# Dual_H_Bridge_and_Accessories.net
KiCad netlist of a schematic drawn in EAGLE
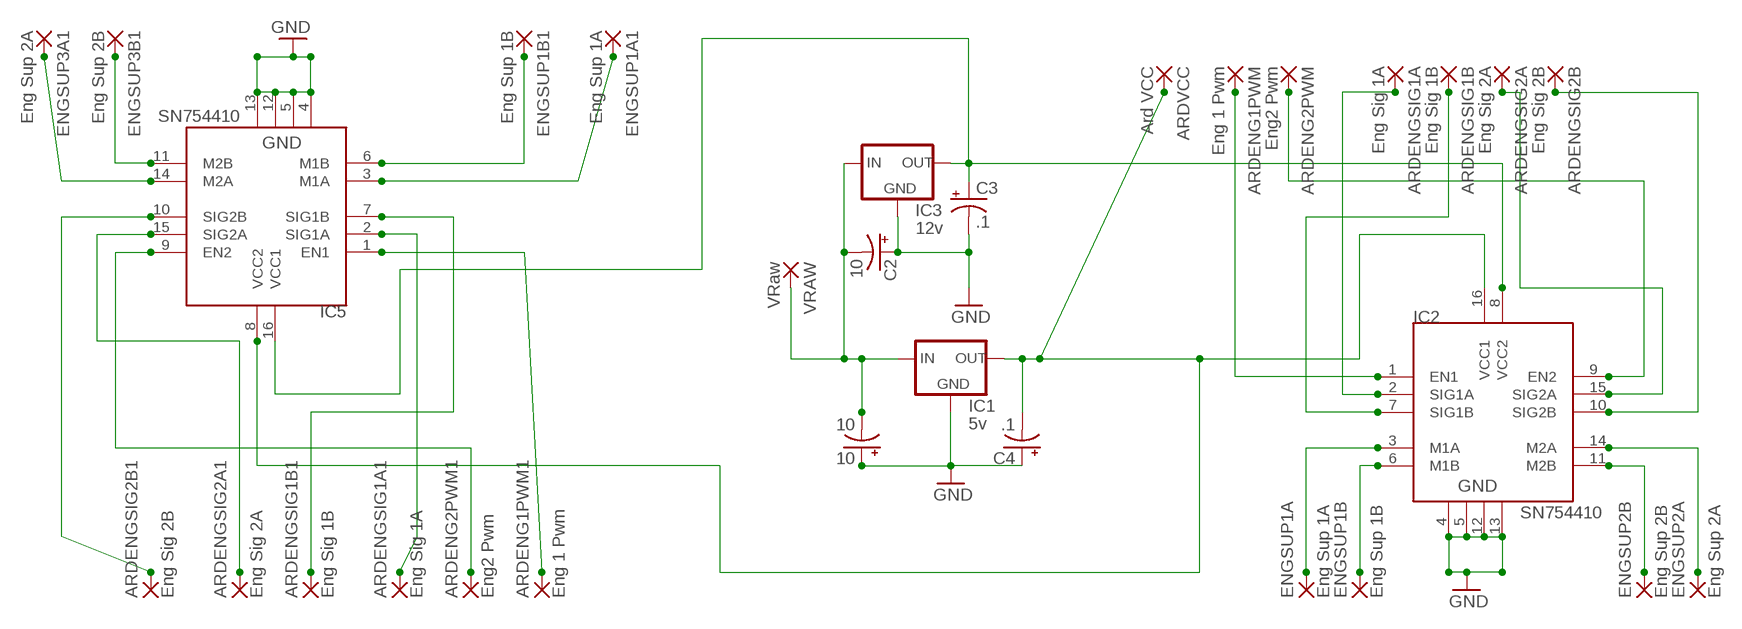
[diagram p0: schematic, sheet 1]

(export (version "E")
  (design (tool "Eeschema 10.0.6"))
  (components
    (comp (ref "10")
      (value "10")
      (footprint "eagle-import:CPOL-RADIAL-10UF-25V")
      (libsource (lib "eagle-import") (part "CAP_POLPTH2"))
    )
    (comp (ref "ARDENG1PWM")
      (value "Eng 1 Pwm")
      (footprint "eagle-import:3,17_1,3")
      (libsource (lib "eagle-import") (part "3,17/1,3"))
    )
    (comp (ref "ARDENG1PWM1")
      (value "Eng 1 Pwm")
      (footprint "eagle-import:3,17_1,3")
      (libsource (lib "eagle-import") (part "3,17/1,3"))
    )
    (comp (ref "ARDENG2PWM")
      (value "Eng2 Pwm")
      (footprint "eagle-import:3,17_1,3")
      (libsource (lib "eagle-import") (part "3,17/1,3"))
    )
    (comp (ref "ARDENG2PWM1")
      (value "Eng2 Pwm")
      (footprint "eagle-import:3,17_1,3")
      (libsource (lib "eagle-import") (part "3,17/1,3"))
    )
    (comp (ref "ARDENGSIG1A")
      (value "Eng Sig 1A")
      (footprint "eagle-import:3,17_1,3")
      (libsource (lib "eagle-import") (part "3,17/1,3"))
    )
    (comp (ref "ARDENGSIG1A1")
      (value "Eng Sig 1A")
      (footprint "eagle-import:3,17_1,3")
      (libsource (lib "eagle-import") (part "3,17/1,3"))
    )
    (comp (ref "ARDENGSIG1B")
      (value "Eng Sig 1B")
      (footprint "eagle-import:3,17_1,3")
      (libsource (lib "eagle-import") (part "3,17/1,3"))
    )
    (comp (ref "ARDENGSIG1B1")
      (value "Eng Sig 1B")
      (footprint "eagle-import:3,17_1,3")
      (libsource (lib "eagle-import") (part "3,17/1,3"))
    )
    (comp (ref "ARDENGSIG2A")
      (value "Eng Sig 2A")
      (footprint "eagle-import:3,17_1,3")
      (libsource (lib "eagle-import") (part "3,17/1,3"))
    )
    (comp (ref "ARDENGSIG2A1")
      (value "Eng Sig 2A")
      (footprint "eagle-import:3,17_1,3")
      (libsource (lib "eagle-import") (part "3,17/1,3"))
    )
    (comp (ref "ARDENGSIG2B")
      (value "Eng Sig 2B")
      (footprint "eagle-import:3,17_1,3")
      (libsource (lib "eagle-import") (part "3,17/1,3"))
    )
    (comp (ref "ARDENGSIG2B1")
      (value "Eng Sig 2B")
      (footprint "eagle-import:3,17_1,3")
      (libsource (lib "eagle-import") (part "3,17/1,3"))
    )
    (comp (ref "ARDVCC")
      (value "Ard VCC")
      (footprint "eagle-import:3,17_1,3")
      (libsource (lib "eagle-import") (part "3,17/1,3"))
    )
    (comp (ref "C2")
      (value "10")
      (footprint "eagle-import:CPOL-RADIAL-10UF-25V")
      (libsource (lib "eagle-import") (part "CAP_POLPTH2"))
    )
    (comp (ref "C3")
      (value ".1")
      (footprint "eagle-import:CPOL-RADIAL-10UF-25V")
      (libsource (lib "eagle-import") (part "CAP_POLPTH2"))
    )
    (comp (ref "C4")
      (value ".1")
      (footprint "eagle-import:CPOL-RADIAL-10UF-25V")
      (libsource (lib "eagle-import") (part "CAP_POLPTH2"))
    )
    (comp (ref "ENGSUP1A")
      (value "Eng Sup 1A")
      (footprint "eagle-import:3,17_1,3")
      (libsource (lib "eagle-import") (part "3,17/1,3"))
    )
    (comp (ref "ENGSUP1A1")
      (value "Eng Sup 1A")
      (footprint "eagle-import:3,17_1,3")
      (libsource (lib "eagle-import") (part "3,17/1,3"))
    )
    (comp (ref "ENGSUP1B")
      (value "Eng Sup 1B")
      (footprint "eagle-import:3,17_1,3")
      (libsource (lib "eagle-import") (part "3,17/1,3"))
    )
    (comp (ref "ENGSUP1B1")
      (value "Eng Sup 1B")
      (footprint "eagle-import:3,17_1,3")
      (libsource (lib "eagle-import") (part "3,17/1,3"))
    )
    (comp (ref "ENGSUP2A")
      (value "Eng Sup 2A")
      (footprint "eagle-import:3,17_1,3")
      (libsource (lib "eagle-import") (part "3,17/1,3"))
    )
    (comp (ref "ENGSUP2B")
      (value "Eng Sup 2B")
      (footprint "eagle-import:3,17_1,3")
      (libsource (lib "eagle-import") (part "3,17/1,3"))
    )
    (comp (ref "ENGSUP3A1")
      (value "Eng Sup 2A")
      (footprint "eagle-import:3,17_1,3")
      (libsource (lib "eagle-import") (part "3,17/1,3"))
    )
    (comp (ref "ENGSUP3B1")
      (value "Eng Sup 2B")
      (footprint "eagle-import:3,17_1,3")
      (libsource (lib "eagle-import") (part "3,17/1,3"))
    )
    (comp (ref "IC1")
      (value "5v")
      (footprint "eagle-import:78XXL")
      (libsource (lib "eagle-import") (part "78XXL"))
    )
    (comp (ref "IC2")
      (value "SN754410")
      (footprint "eagle-import:DIP16")
      (libsource (lib "eagle-import") (part "SN754410"))
    )
    (comp (ref "IC3")
      (value "12v")
      (footprint "eagle-import:78XXL")
      (libsource (lib "eagle-import") (part "78XXL"))
    )
    (comp (ref "IC5")
      (value "SN754410")
      (footprint "eagle-import:DIP16")
      (libsource (lib "eagle-import") (part "SN754410"))
    )
    (comp (ref "VRAW")
      (value "VRaw")
      (footprint "eagle-import:3,81_1,4")
      (libsource (lib "eagle-import") (part "3,81/1,4"))
    )
  )
  (nets
    (net (code "1") (name "GND") (class "Default")
      (node (ref "10") (pin "1") (pinfunction "+_1") (pintype "passive"))
      (node (ref "C2") (pin "1") (pinfunction "+_1") (pintype "passive"))
      (node (ref "C3") (pin "2") (pinfunction "-_2") (pintype "passive"))
      (node (ref "C4") (pin "1") (pinfunction "+_1") (pintype "passive"))
      (node (ref "IC1") (pin "GND") (pinfunction "GND_GND") (pintype "input"))
      (node (ref "IC2") (pin "12") (pinfunction "P12_12") (pintype "power_in"))
      (node (ref "IC2") (pin "13") (pinfunction "P13_13") (pintype "power_in"))
      (node (ref "IC2") (pin "4") (pinfunction "P4_4") (pintype "power_in"))
      (node (ref "IC2") (pin "5") (pinfunction "P5_5") (pintype "power_in"))
      (node (ref "IC3") (pin "GND") (pinfunction "GND_GND") (pintype "input"))
      (node (ref "IC5") (pin "12") (pinfunction "P12_12") (pintype "power_in"))
      (node (ref "IC5") (pin "13") (pinfunction "P13_13") (pintype "power_in"))
      (node (ref "IC5") (pin "4") (pinfunction "P4_4") (pintype "power_in"))
      (node (ref "IC5") (pin "5") (pinfunction "P5_5") (pintype "power_in"))
    )
    (net (code "2") (name "Net-(10--)") (class "Default")
      (node (ref "10") (pin "2") (pinfunction "-_2") (pintype "passive"))
      (node (ref "C2") (pin "2") (pinfunction "-_2") (pintype "passive"))
      (node (ref "IC1") (pin "IN") (pinfunction "IN_IN") (pintype "input"))
      (node (ref "IC3") (pin "IN") (pinfunction "IN_IN") (pintype "input"))
      (node (ref "VRAW") (pin "1") (pinfunction "P_1") (pintype "passive"))
    )
    (net (code "3") (name "Net-(ARDENG1PWM-P)") (class "Default")
      (node (ref "ARDENG1PWM") (pin "1") (pinfunction "P_1") (pintype "passive"))
      (node (ref "IC2") (pin "1") (pinfunction "EN1_1") (pintype "bidirectional"))
    )
    (net (code "4") (name "Net-(ARDENG1PWM1-P)") (class "Default")
      (node (ref "ARDENG1PWM1") (pin "1") (pinfunction "P_1") (pintype "passive"))
      (node (ref "IC5") (pin "1") (pinfunction "EN1_1") (pintype "bidirectional"))
    )
    (net (code "5") (name "Net-(ARDENG2PWM-P)") (class "Default")
      (node (ref "ARDENG2PWM") (pin "1") (pinfunction "P_1") (pintype "passive"))
      (node (ref "IC2") (pin "9") (pinfunction "EN2_9") (pintype "bidirectional"))
    )
    (net (code "6") (name "Net-(ARDENG2PWM1-P)") (class "Default")
      (node (ref "ARDENG2PWM1") (pin "1") (pinfunction "P_1") (pintype "passive"))
      (node (ref "IC5") (pin "9") (pinfunction "EN2_9") (pintype "bidirectional"))
    )
    (net (code "7") (name "Net-(ARDENGSIG1A-P)") (class "Default")
      (node (ref "ARDENGSIG1A") (pin "1") (pinfunction "P_1") (pintype "passive"))
      (node (ref "IC2") (pin "2") (pinfunction "SIG1A_2") (pintype "bidirectional"))
    )
    (net (code "8") (name "Net-(ARDENGSIG1A1-P)") (class "Default")
      (node (ref "ARDENGSIG1A1") (pin "1") (pinfunction "P_1") (pintype "passive"))
      (node (ref "IC5") (pin "2") (pinfunction "SIG1A_2") (pintype "bidirectional"))
    )
    (net (code "9") (name "Net-(ARDENGSIG1B-P)") (class "Default")
      (node (ref "ARDENGSIG1B") (pin "1") (pinfunction "P_1") (pintype "passive"))
      (node (ref "IC2") (pin "7") (pinfunction "SIG1B_7") (pintype "bidirectional"))
    )
    (net (code "10") (name "Net-(ARDENGSIG1B1-P)") (class "Default")
      (node (ref "ARDENGSIG1B1") (pin "1") (pinfunction "P_1") (pintype "passive"))
      (node (ref "IC5") (pin "7") (pinfunction "SIG1B_7") (pintype "bidirectional"))
    )
    (net (code "11") (name "Net-(ARDENGSIG2A-P)") (class "Default")
      (node (ref "ARDENGSIG2A") (pin "1") (pinfunction "P_1") (pintype "passive"))
      (node (ref "IC2") (pin "15") (pinfunction "SIG2A_15") (pintype "bidirectional"))
    )
    (net (code "12") (name "Net-(ARDENGSIG2A1-P)") (class "Default")
      (node (ref "ARDENGSIG2A1") (pin "1") (pinfunction "P_1") (pintype "passive"))
      (node (ref "IC5") (pin "15") (pinfunction "SIG2A_15") (pintype "bidirectional"))
    )
    (net (code "13") (name "Net-(ARDENGSIG2B-P)") (class "Default")
      (node (ref "ARDENGSIG2B") (pin "1") (pinfunction "P_1") (pintype "passive"))
      (node (ref "IC2") (pin "10") (pinfunction "SIG2B_10") (pintype "bidirectional"))
    )
    (net (code "14") (name "Net-(ARDENGSIG2B1-P)") (class "Default")
      (node (ref "ARDENGSIG2B1") (pin "1") (pinfunction "P_1") (pintype "passive"))
      (node (ref "IC5") (pin "10") (pinfunction "SIG2B_10") (pintype "bidirectional"))
    )
    (net (code "15") (name "Net-(ARDVCC-P)") (class "Default")
      (node (ref "ARDVCC") (pin "1") (pinfunction "P_1") (pintype "passive"))
      (node (ref "C4") (pin "2") (pinfunction "-_2") (pintype "passive"))
      (node (ref "IC1") (pin "OUT") (pinfunction "OUT_OUT") (pintype "passive"))
      (node (ref "IC2") (pin "16") (pinfunction "VCC1_16") (pintype "power_in"))
      (node (ref "IC5") (pin "8") (pinfunction "VCC2_8") (pintype "power_in"))
    )
    (net (code "16") (name "Net-(C3-+)") (class "Default")
      (node (ref "C3") (pin "1") (pinfunction "+_1") (pintype "passive"))
      (node (ref "IC2") (pin "8") (pinfunction "VCC2_8") (pintype "power_in"))
      (node (ref "IC3") (pin "OUT") (pinfunction "OUT_OUT") (pintype "passive"))
      (node (ref "IC5") (pin "16") (pinfunction "VCC1_16") (pintype "power_in"))
    )
    (net (code "17") (name "Net-(ENGSUP1A-P)") (class "Default")
      (node (ref "ENGSUP1A") (pin "1") (pinfunction "P_1") (pintype "passive"))
      (node (ref "IC2") (pin "3") (pinfunction "M1A_3") (pintype "bidirectional"))
    )
    (net (code "18") (name "Net-(ENGSUP1A1-P)") (class "Default")
      (node (ref "ENGSUP1A1") (pin "1") (pinfunction "P_1") (pintype "passive"))
      (node (ref "IC5") (pin "3") (pinfunction "M1A_3") (pintype "bidirectional"))
    )
    (net (code "19") (name "Net-(ENGSUP1B-P)") (class "Default")
      (node (ref "ENGSUP1B") (pin "1") (pinfunction "P_1") (pintype "passive"))
      (node (ref "IC2") (pin "6") (pinfunction "M1B_6") (pintype "bidirectional"))
    )
    (net (code "20") (name "Net-(ENGSUP1B1-P)") (class "Default")
      (node (ref "ENGSUP1B1") (pin "1") (pinfunction "P_1") (pintype "passive"))
      (node (ref "IC5") (pin "6") (pinfunction "M1B_6") (pintype "bidirectional"))
    )
    (net (code "21") (name "Net-(ENGSUP2A-P)") (class "Default")
      (node (ref "ENGSUP2A") (pin "1") (pinfunction "P_1") (pintype "passive"))
      (node (ref "IC2") (pin "14") (pinfunction "M2A_14") (pintype "bidirectional"))
    )
    (net (code "22") (name "Net-(ENGSUP2B-P)") (class "Default")
      (node (ref "ENGSUP2B") (pin "1") (pinfunction "P_1") (pintype "passive"))
      (node (ref "IC2") (pin "11") (pinfunction "M2B_11") (pintype "bidirectional"))
    )
    (net (code "23") (name "Net-(ENGSUP3A1-P)") (class "Default")
      (node (ref "ENGSUP3A1") (pin "1") (pinfunction "P_1") (pintype "passive"))
      (node (ref "IC5") (pin "14") (pinfunction "M2A_14") (pintype "bidirectional"))
    )
    (net (code "24") (name "Net-(ENGSUP3B1-P)") (class "Default")
      (node (ref "ENGSUP3B1") (pin "1") (pinfunction "P_1") (pintype "passive"))
      (node (ref "IC5") (pin "11") (pinfunction "M2B_11") (pintype "bidirectional"))
    )
  )
)
